# NRF24L01P.net
KiCad netlist of a schematic drawn in Altium Designer
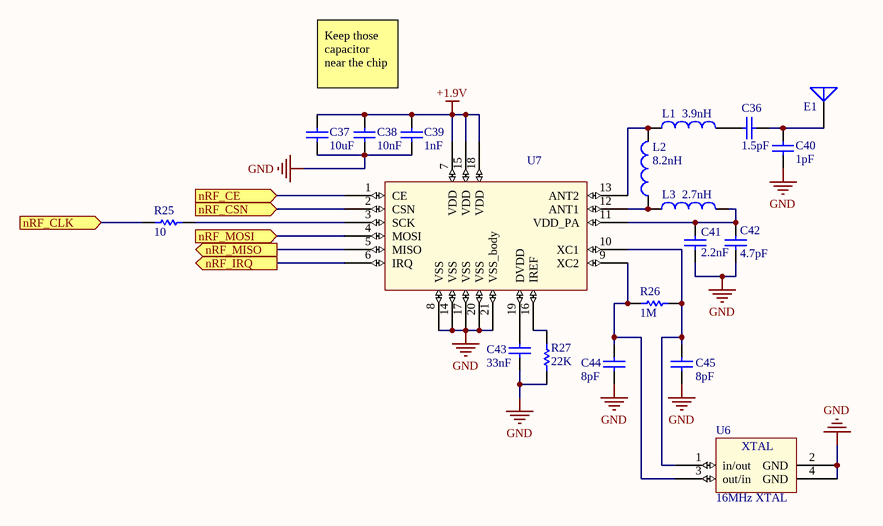
[diagram p0: NRF24L01P.SchDoc]

(export (version "E")
  (design (tool "Eeschema 10.0.6"))
  (components
    (comp (ref "C36")
      (value "1.5pF")
      (footprint "0201_Custom")
      (description "Capacitor (Semiconductor SIM Model)")
      (fields (field (name "PUBLISHER") "Altium Limited"))
      (libsource (lib "Miscellaneous Devices") (part "Cap Semi"))
    )
    (comp (ref "C37")
      (value "10uF")
      (footprint "0402")
      (description "Capacitor (Semiconductor SIM Model)")
      (fields (field (name "PUBLISHER") "Altium Limited"))
      (libsource (lib "Miscellaneous Devices") (part "Cap Semi"))
    )
    (comp (ref "C38")
      (value "10nF")
      (footprint "0201_Custom")
      (description "Capacitor (Semiconductor SIM Model)")
      (fields (field (name "PUBLISHER") "Altium Limited"))
      (libsource (lib "Miscellaneous Devices") (part "Cap Semi"))
    )
    (comp (ref "C39")
      (value "1nF")
      (footprint "0201_Custom")
      (description "Capacitor (Semiconductor SIM Model)")
      (fields (field (name "PUBLISHER") "Altium Limited"))
      (libsource (lib "Miscellaneous Devices") (part "Cap Semi"))
    )
    (comp (ref "C40")
      (value "1pF")
      (footprint "0201_Custom")
      (description "Capacitor (Semiconductor SIM Model)")
      (fields (field (name "PUBLISHER") "Altium Limited"))
      (libsource (lib "Miscellaneous Devices") (part "Cap Semi"))
    )
    (comp (ref "C41")
      (value "2.2nF")
      (footprint "0201_Custom")
      (description "Capacitor (Semiconductor SIM Model)")
      (fields (field (name "PUBLISHER") "Altium Limited"))
      (libsource (lib "Miscellaneous Devices") (part "Cap Semi"))
    )
    (comp (ref "C42")
      (value "4.7pF")
      (footprint "0201_Custom")
      (description "Capacitor (Semiconductor SIM Model)")
      (fields (field (name "PUBLISHER") "Altium Limited"))
      (libsource (lib "Miscellaneous Devices") (part "Cap Semi"))
    )
    (comp (ref "C43")
      (value "33nF")
      (footprint "0201_Custom")
      (description "Capacitor (Semiconductor SIM Model)")
      (fields (field (name "PUBLISHER") "Altium Limited"))
      (libsource (lib "Miscellaneous Devices") (part "Cap Semi"))
    )
    (comp (ref "C44")
      (value "8pF")
      (footprint "0201_Custom")
      (description "Capacitor (Semiconductor SIM Model)")
      (fields (field (name "PUBLISHER") "Altium Limited"))
      (libsource (lib "Miscellaneous Devices") (part "Cap Semi"))
    )
    (comp (ref "C45")
      (value "8pF")
      (footprint "0201_Custom")
      (description "Capacitor (Semiconductor SIM Model)")
      (fields (field (name "PUBLISHER") "Altium Limited"))
      (libsource (lib "Miscellaneous Devices") (part "Cap Semi"))
    )
    (comp (ref "E1")
      (value "~")
      (footprint "ANT-2.45-CHP-B")
      (description "Generic Antenna")
      (fields (field (name "PUBLISHER") "Altium Limited"))
      (libsource (lib "Miscellaneous Devices") (part "Antenna"))
    )
    (comp (ref "L1")
      (value "3.9nH")
      (footprint "0201_Custom")
      (description "Inductor")
      (fields (field (name "PUBLISHER") "Altium Limited"))
      (libsource (lib "Miscellaneous Devices") (part "Inductor"))
    )
    (comp (ref "L2")
      (value "8.2nH")
      (footprint "0201_Custom")
      (description "Inductor")
      (fields (field (name "PUBLISHER") "Altium Limited"))
      (libsource (lib "Miscellaneous Devices") (part "Inductor"))
    )
    (comp (ref "L3")
      (value "2.7nH")
      (footprint "0201_Custom")
      (description "Inductor")
      (fields (field (name "PUBLISHER") "Altium Limited"))
      (libsource (lib "Miscellaneous Devices") (part "Inductor"))
    )
    (comp (ref "R25")
      (value "10")
      (footprint "0201_Custom")
      (description "Semiconductor Resistor")
      (fields (field (name "PUBLISHER") "Altium Limited"))
      (libsource (lib "Miscellaneous Devices") (part "Res Semi"))
    )
    (comp (ref "R26")
      (value "1M")
      (footprint "0201_Custom")
      (description "Semiconductor Resistor")
      (fields (field (name "PUBLISHER") "Altium Limited"))
      (libsource (lib "Miscellaneous Devices") (part "Res Semi"))
    )
    (comp (ref "R27")
      (value "22K")
      (footprint "0201_Custom")
      (description "Semiconductor Resistor")
      (fields (field (name "PUBLISHER") "Altium Limited"))
      (libsource (lib "Miscellaneous Devices") (part "Res Semi"))
    )
    (comp (ref "U6")
      (value "16MHz XTAL")
      (footprint "8Y-16.000MAAV-T")
      (description "SMD 16 MHz XTAL")
      (libsource (lib "headstage_parts") (part "8Y-16.000MAAV-T"))
    )
    (comp (ref "U7")
      (value "~")
      (footprint "QFN50P400X400-20W5M")
      (description "nRF24L01+")
      (libsource (lib "new_headstage_parts") (part "nRF24L01p"))
    )
  )
  (nets
    (net (code "1") (name "+1.9V") (class "Default")
      (node (ref "C37") (pin "2") (pinfunction "2_2") (pintype "passive"))
      (node (ref "C38") (pin "2") (pinfunction "2_2") (pintype "passive"))
      (node (ref "C39") (pin "2") (pinfunction "2_2") (pintype "passive"))
      (node (ref "U7") (pin "15") (pinfunction "VDD_15") (pintype "bidirectional"))
      (node (ref "U7") (pin "18") (pinfunction "VDD_18") (pintype "bidirectional"))
      (node (ref "U7") (pin "7") (pinfunction "VDD_7") (pintype "bidirectional"))
    )
    (net (code "2") (name "/nRF_CE") (class "Default")
      (node (ref "U7") (pin "1") (pinfunction "CE_1") (pintype "bidirectional"))
    )
    (net (code "3") (name "/nRF_CLK") (class "Default")
      (node (ref "R25") (pin "2") (pinfunction "2_2") (pintype "passive"))
    )
    (net (code "4") (name "/nRF_CSN") (class "Default")
      (node (ref "U7") (pin "2") (pinfunction "CSN_2") (pintype "bidirectional"))
    )
    (net (code "5") (name "/nRF_IRQ") (class "Default")
      (node (ref "U7") (pin "6") (pinfunction "IRQ_6") (pintype "bidirectional"))
    )
    (net (code "6") (name "/nRF_MISO") (class "Default")
      (node (ref "U7") (pin "5") (pinfunction "MISO_5") (pintype "bidirectional"))
    )
    (net (code "7") (name "/nRF_MOSI") (class "Default")
      (node (ref "U7") (pin "4") (pinfunction "MOSI_4") (pintype "bidirectional"))
    )
    (net (code "8") (name "GND") (class "Default")
      (node (ref "C37") (pin "1") (pinfunction "1_1") (pintype "passive"))
      (node (ref "C38") (pin "1") (pinfunction "1_1") (pintype "passive"))
      (node (ref "C39") (pin "1") (pinfunction "1_1") (pintype "passive"))
      (node (ref "C40") (pin "2") (pinfunction "2_2") (pintype "passive"))
      (node (ref "C41") (pin "1") (pinfunction "1_1") (pintype "passive"))
      (node (ref "C42") (pin "1") (pinfunction "1_1") (pintype "passive"))
      (node (ref "C43") (pin "1") (pinfunction "1_1") (pintype "passive"))
      (node (ref "C44") (pin "1") (pinfunction "1_1") (pintype "passive"))
      (node (ref "C45") (pin "1") (pinfunction "1_1") (pintype "passive"))
      (node (ref "R27") (pin "1") (pinfunction "1_1") (pintype "passive"))
      (node (ref "U6") (pin "2") (pinfunction "GND_2") (pintype "power_in"))
      (node (ref "U6") (pin "4") (pinfunction "GND_4") (pintype "power_in"))
      (node (ref "U7") (pin "14") (pinfunction "VSS_14") (pintype "bidirectional"))
      (node (ref "U7") (pin "17") (pinfunction "VSS_17") (pintype "bidirectional"))
      (node (ref "U7") (pin "20") (pinfunction "VSS_20") (pintype "bidirectional"))
      (node (ref "U7") (pin "21") (pinfunction "VSS_body_21") (pintype "bidirectional"))
      (node (ref "U7") (pin "8") (pinfunction "VSS_8") (pintype "bidirectional"))
    )
    (net (code "9") (name "Net-(C36-Pad2)") (class "Default")
      (node (ref "C36") (pin "2") (pinfunction "2_2") (pintype "passive"))
      (node (ref "L1") (pin "2") (pinfunction "2_2") (pintype "passive"))
    )
    (net (code "10") (name "Net-(E1-A)") (class "Default")
      (node (ref "C36") (pin "1") (pinfunction "1_1") (pintype "passive"))
      (node (ref "C40") (pin "1") (pinfunction "1_1") (pintype "passive"))
      (node (ref "E1") (pin "1") (pinfunction "A_1") (pintype "passive"))
    )
    (net (code "11") (name "Net-(U6-in{slash}out)") (class "Default")
      (node (ref "C45") (pin "2") (pinfunction "2_2") (pintype "passive"))
      (node (ref "R26") (pin "1") (pinfunction "1_1") (pintype "passive"))
      (node (ref "U6") (pin "1") (pinfunction "in/out_1") (pintype "bidirectional"))
      (node (ref "U7") (pin "10") (pinfunction "XC1_10") (pintype "bidirectional"))
    )
    (net (code "12") (name "Net-(U6-out{slash}in)") (class "Default")
      (node (ref "C44") (pin "2") (pinfunction "2_2") (pintype "passive"))
      (node (ref "R26") (pin "2") (pinfunction "2_2") (pintype "passive"))
      (node (ref "U6") (pin "3") (pinfunction "out/in_3") (pintype "bidirectional"))
      (node (ref "U7") (pin "9") (pinfunction "XC2_9") (pintype "bidirectional"))
    )
    (net (code "13") (name "Net-(U7-ANT1)") (class "Default")
      (node (ref "L2") (pin "1") (pinfunction "1_1") (pintype "passive"))
      (node (ref "L3") (pin "1") (pinfunction "1_1") (pintype "passive"))
      (node (ref "U7") (pin "12") (pinfunction "ANT1_12") (pintype "bidirectional"))
    )
    (net (code "14") (name "Net-(U7-ANT2)") (class "Default")
      (node (ref "L1") (pin "1") (pinfunction "1_1") (pintype "passive"))
      (node (ref "L2") (pin "2") (pinfunction "2_2") (pintype "passive"))
      (node (ref "U7") (pin "13") (pinfunction "ANT2_13") (pintype "bidirectional"))
    )
    (net (code "15") (name "Net-(U7-DVDD)") (class "Default")
      (node (ref "C43") (pin "2") (pinfunction "2_2") (pintype "passive"))
      (node (ref "U7") (pin "19") (pinfunction "DVDD_19") (pintype "bidirectional"))
    )
    (net (code "16") (name "Net-(U7-IREF)") (class "Default")
      (node (ref "R27") (pin "2") (pinfunction "2_2") (pintype "passive"))
      (node (ref "U7") (pin "16") (pinfunction "IREF_16") (pintype "bidirectional"))
    )
    (net (code "17") (name "Net-(U7-SCK)") (class "Default")
      (node (ref "R25") (pin "1") (pinfunction "1_1") (pintype "passive"))
      (node (ref "U7") (pin "3") (pinfunction "SCK_3") (pintype "bidirectional"))
    )
    (net (code "18") (name "Net-(U7-VDD_PA)") (class "Default")
      (node (ref "C41") (pin "2") (pinfunction "2_2") (pintype "passive"))
      (node (ref "C42") (pin "2") (pinfunction "2_2") (pintype "passive"))
      (node (ref "L3") (pin "2") (pinfunction "2_2") (pintype "passive"))
      (node (ref "U7") (pin "11") (pinfunction "VDD_PA_11") (pintype "bidirectional"))
    )
  )
)
